# W506C.net
KiCad netlist of a schematic drawn in EAGLE
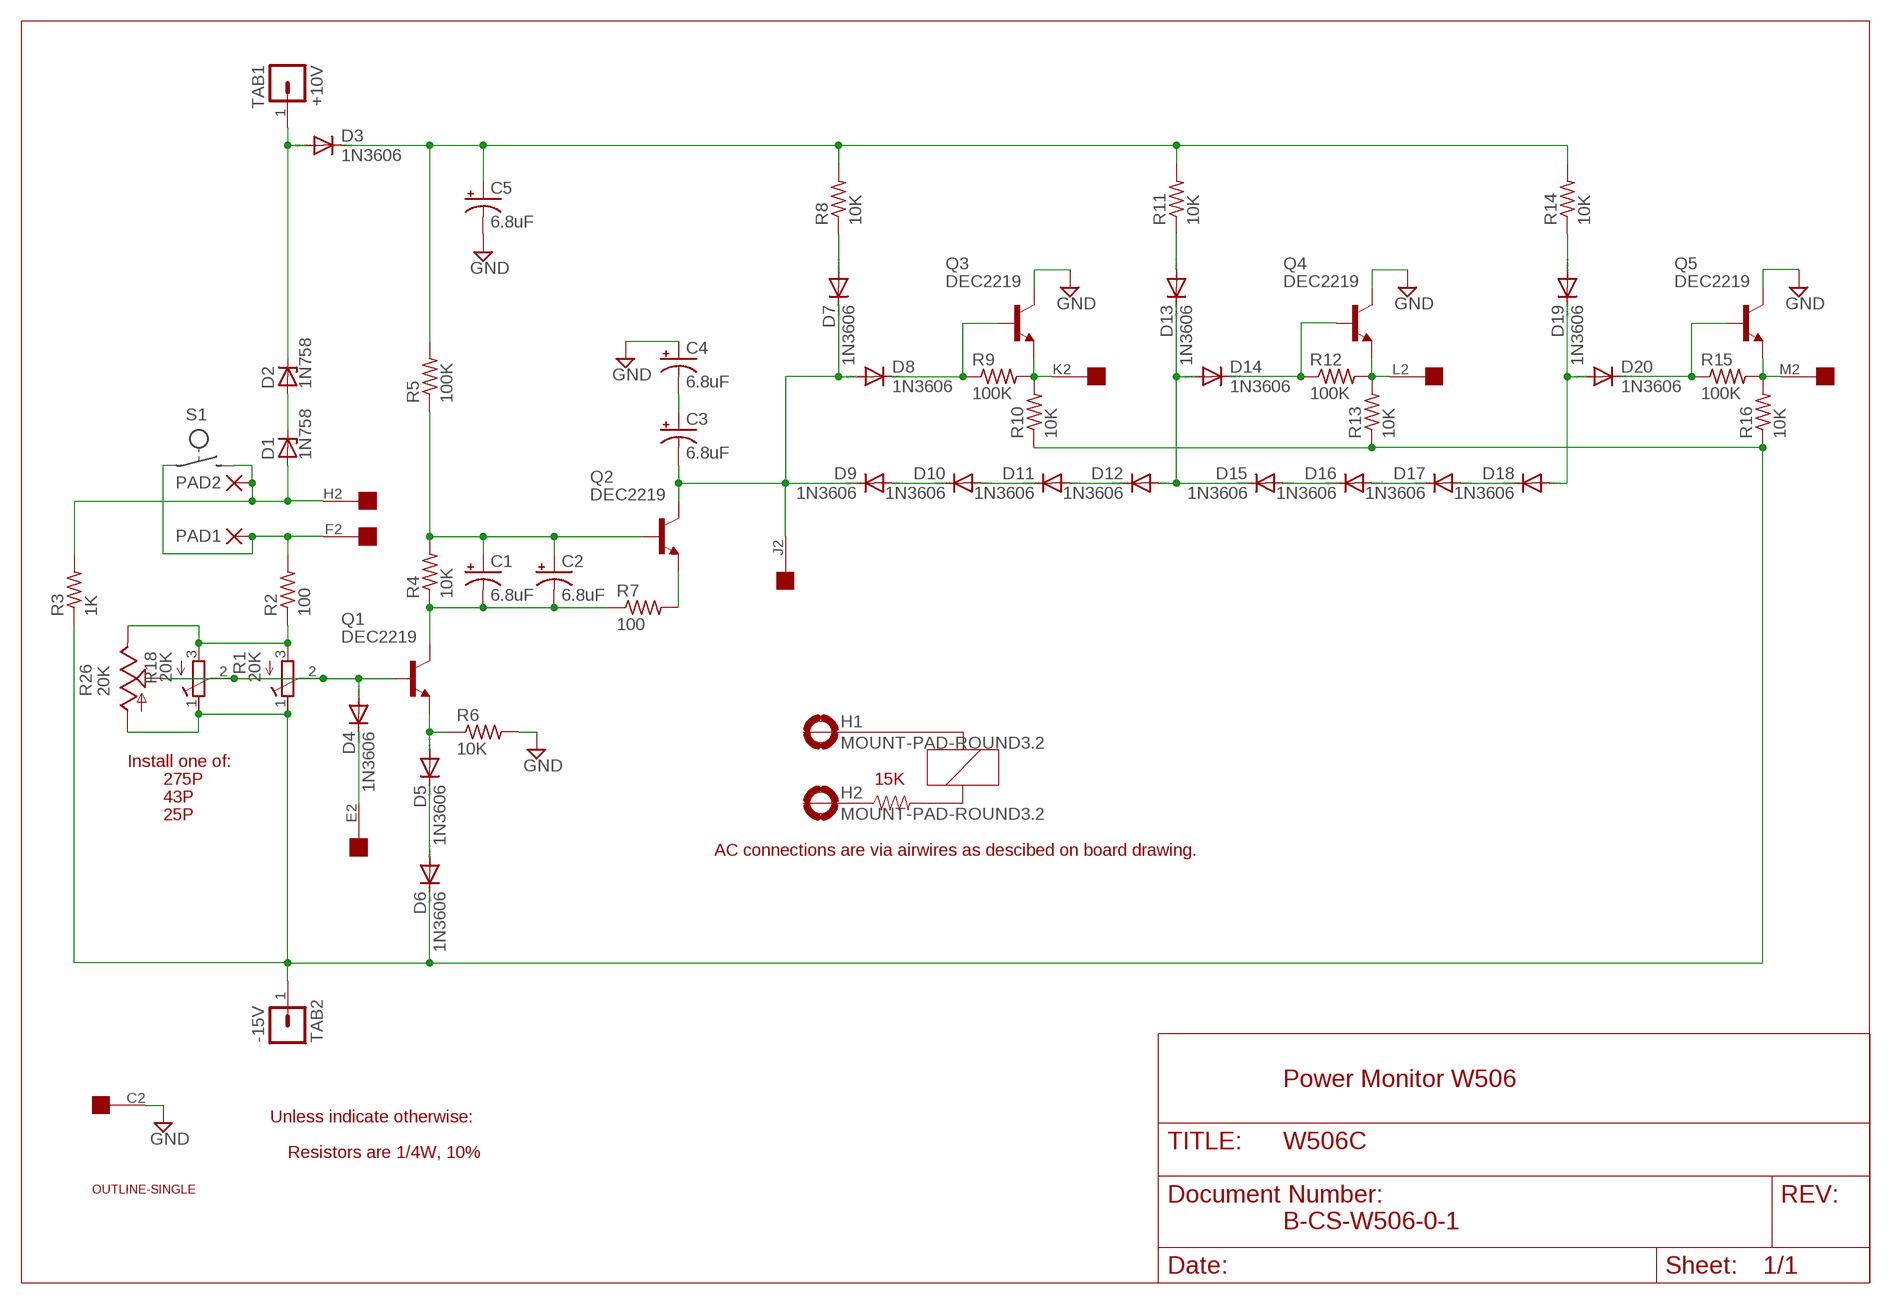
[diagram p0: schematic, sheet 1]

(export (version "E")
  (design (tool "Eeschema 10.0.6"))
  (components
    (comp (ref "C1")
      (value "6.8uF")
      (footprint "eagle-import:E15-5")
      (libsource (lib "eagle-import") (part "CPOL-USE15-5AXIAL"))
    )
    (comp (ref "C2")
      (value "6.8uF")
      (footprint "eagle-import:E15-5")
      (libsource (lib "eagle-import") (part "CPOL-USE15-5AXIAL"))
    )
    (comp (ref "C3")
      (value "6.8uF")
      (footprint "eagle-import:E15-5")
      (libsource (lib "eagle-import") (part "CPOL-USE15-5AXIAL"))
    )
    (comp (ref "C4")
      (value "6.8uF")
      (footprint "eagle-import:E15-5")
      (libsource (lib "eagle-import") (part "CPOL-USE15-5AXIAL"))
    )
    (comp (ref "C5")
      (value "6.8uF")
      (footprint "eagle-import:E15-5")
      (libsource (lib "eagle-import") (part "CPOL-USE15-5AXIAL"))
    )
    (comp (ref "D1")
      (value "1N758")
      (footprint "eagle-import:DO35Z10")
      (libsource (lib "eagle-import") (part "ZENER-DIODEDO35Z10"))
    )
    (comp (ref "D2")
      (value "1N758")
      (footprint "eagle-import:DO35Z10")
      (libsource (lib "eagle-import") (part "ZENER-DIODEDO35Z10"))
    )
    (comp (ref "D3")
      (value "1N3606")
      (footprint "eagle-import:DO35-10")
      (libsource (lib "eagle-import") (part "1N4148DO35-10"))
    )
    (comp (ref "D4")
      (value "1N3606")
      (footprint "eagle-import:DO35-10")
      (libsource (lib "eagle-import") (part "1N4148DO35-10"))
    )
    (comp (ref "D5")
      (value "1N3606")
      (footprint "eagle-import:DO35-10")
      (libsource (lib "eagle-import") (part "1N4148DO35-10"))
    )
    (comp (ref "D6")
      (value "1N3606")
      (footprint "eagle-import:DO35-10")
      (libsource (lib "eagle-import") (part "1N4148DO35-10"))
    )
    (comp (ref "D7")
      (value "1N3606")
      (footprint "eagle-import:DO35-10")
      (libsource (lib "eagle-import") (part "1N4148DO35-10"))
    )
    (comp (ref "D8")
      (value "1N3606")
      (footprint "eagle-import:DO35-10")
      (libsource (lib "eagle-import") (part "1N4148DO35-10"))
    )
    (comp (ref "D9")
      (value "1N3606")
      (footprint "eagle-import:DO35-10")
      (libsource (lib "eagle-import") (part "1N4148DO35-10"))
    )
    (comp (ref "D10")
      (value "1N3606")
      (footprint "eagle-import:DO35-10")
      (libsource (lib "eagle-import") (part "1N4148DO35-10"))
    )
    (comp (ref "D11")
      (value "1N3606")
      (footprint "eagle-import:DO35-10")
      (libsource (lib "eagle-import") (part "1N4148DO35-10"))
    )
    (comp (ref "D12")
      (value "1N3606")
      (footprint "eagle-import:DO35-10")
      (libsource (lib "eagle-import") (part "1N4148DO35-10"))
    )
    (comp (ref "D13")
      (value "1N3606")
      (footprint "eagle-import:DO35-10")
      (libsource (lib "eagle-import") (part "1N4148DO35-10"))
    )
    (comp (ref "D14")
      (value "1N3606")
      (footprint "eagle-import:DO35-10")
      (libsource (lib "eagle-import") (part "1N4148DO35-10"))
    )
    (comp (ref "D15")
      (value "1N3606")
      (footprint "eagle-import:DO35-10")
      (libsource (lib "eagle-import") (part "1N4148DO35-10"))
    )
    (comp (ref "D16")
      (value "1N3606")
      (footprint "eagle-import:DO35-10")
      (libsource (lib "eagle-import") (part "1N4148DO35-10"))
    )
    (comp (ref "D17")
      (value "1N3606")
      (footprint "eagle-import:DO35-10")
      (libsource (lib "eagle-import") (part "1N4148DO35-10"))
    )
    (comp (ref "D18")
      (value "1N3606")
      (footprint "eagle-import:DO35-10")
      (libsource (lib "eagle-import") (part "1N4148DO35-10"))
    )
    (comp (ref "D19")
      (value "1N3606")
      (footprint "eagle-import:DO35-10")
      (libsource (lib "eagle-import") (part "1N4148DO35-10"))
    )
    (comp (ref "D20")
      (value "1N3606")
      (footprint "eagle-import:DO35-10")
      (libsource (lib "eagle-import") (part "1N4148DO35-10"))
    )
    (comp (ref "EDGE")
      (value "EDGE-1")
      (footprint "eagle-import:EDGE-CON1")
      (libsource (lib "eagle-import") (part "EDGE-1"))
    )
    (comp (ref "H1")
      (value "MOUNT-PAD-ROUND3.2")
      (footprint "eagle-import:3,2-PAD")
      (libsource (lib "eagle-import") (part "MOUNT-PAD-ROUND3.2"))
    )
    (comp (ref "H2")
      (value "MOUNT-PAD-ROUND3.2")
      (footprint "eagle-import:3,2-PAD")
      (libsource (lib "eagle-import") (part "MOUNT-PAD-ROUND3.2"))
    )
    (comp (ref "PAD1")
      (value "PAD-0320")
      (footprint "eagle-import:0320")
      (libsource (lib "eagle-import") (part "PAD-0320"))
    )
    (comp (ref "PAD2")
      (value "PAD-0320")
      (footprint "eagle-import:0320")
      (libsource (lib "eagle-import") (part "PAD-0320"))
    )
    (comp (ref "Q1")
      (value "DEC2219")
      (footprint "eagle-import:TO5")
      (libsource (lib "eagle-import") (part "2N2102"))
    )
    (comp (ref "Q2")
      (value "DEC2219")
      (footprint "eagle-import:TO5")
      (libsource (lib "eagle-import") (part "2N2102"))
    )
    (comp (ref "Q3")
      (value "DEC2219")
      (footprint "eagle-import:TO5")
      (libsource (lib "eagle-import") (part "2N2102"))
    )
    (comp (ref "Q4")
      (value "DEC2219")
      (footprint "eagle-import:TO5")
      (libsource (lib "eagle-import") (part "2N2102"))
    )
    (comp (ref "Q5")
      (value "DEC2219")
      (footprint "eagle-import:TO5")
      (libsource (lib "eagle-import") (part "2N2102"))
    )
    (comp (ref "R1")
      (value "20K")
      (footprint "eagle-import:3006Y")
      (libsource (lib "eagle-import") (part "275P"))
    )
    (comp (ref "R2")
      (value "100")
      (footprint "eagle-import:0207_10")
      (libsource (lib "eagle-import") (part "R-US_0207/10"))
    )
    (comp (ref "R3")
      (value "1K")
      (footprint "eagle-import:0207_10")
      (libsource (lib "eagle-import") (part "R-US_0207/10"))
    )
    (comp (ref "R4")
      (value "10K")
      (footprint "eagle-import:0207_10")
      (libsource (lib "eagle-import") (part "R-US_0207/10"))
    )
    (comp (ref "R5")
      (value "100K")
      (footprint "eagle-import:0207_10")
      (libsource (lib "eagle-import") (part "R-US_0207/10"))
    )
    (comp (ref "R6")
      (value "10K")
      (footprint "eagle-import:0207_10")
      (libsource (lib "eagle-import") (part "R-US_0207/10"))
    )
    (comp (ref "R7")
      (value "100")
      (footprint "eagle-import:0207_10")
      (libsource (lib "eagle-import") (part "R-US_0207/10"))
    )
    (comp (ref "R8")
      (value "10K")
      (footprint "eagle-import:0207_10")
      (libsource (lib "eagle-import") (part "R-US_0207/10"))
    )
    (comp (ref "R9")
      (value "100K")
      (footprint "eagle-import:0207_10")
      (libsource (lib "eagle-import") (part "R-US_0207/10"))
    )
    (comp (ref "R10")
      (value "10K")
      (footprint "eagle-import:0207_10")
      (libsource (lib "eagle-import") (part "R-US_0207/10"))
    )
    (comp (ref "R11")
      (value "10K")
      (footprint "eagle-import:0207_10")
      (libsource (lib "eagle-import") (part "R-US_0207/10"))
    )
    (comp (ref "R12")
      (value "100K")
      (footprint "eagle-import:0207_10")
      (libsource (lib "eagle-import") (part "R-US_0207/10"))
    )
    (comp (ref "R13")
      (value "10K")
      (footprint "eagle-import:0207_10")
      (libsource (lib "eagle-import") (part "R-US_0207/10"))
    )
    (comp (ref "R14")
      (value "10K")
      (footprint "eagle-import:0207_10")
      (libsource (lib "eagle-import") (part "R-US_0207/10"))
    )
    (comp (ref "R15")
      (value "100K")
      (footprint "eagle-import:0207_10")
      (libsource (lib "eagle-import") (part "R-US_0207/10"))
    )
    (comp (ref "R16")
      (value "10K")
      (footprint "eagle-import:0207_10")
      (libsource (lib "eagle-import") (part "R-US_0207/10"))
    )
    (comp (ref "R18")
      (value "20K")
      (footprint "eagle-import:RTRIM43P")
      (libsource (lib "eagle-import") (part "R-TRIMM43P"))
    )
    (comp (ref "R26")
      (value "20K")
      (footprint "eagle-import:B25P")
      (libsource (lib "eagle-import") (part "TRIM_US-B25P"))
    )
    (comp (ref "TAB1")
      (value "+10V")
      (footprint "eagle-import:SPADELUG")
      (libsource (lib "eagle-import") (part "LUG"))
    )
    (comp (ref "TAB2")
      (value "-15V")
      (footprint "eagle-import:SPADELUG")
      (libsource (lib "eagle-import") (part "LUG"))
    )
    (comp (ref "U$1")
      (value "OUTLINE-SINGLE")
      (footprint "eagle-import:SINGLE")
      (libsource (lib "eagle-import") (part "OUTLINE-SINGLE"))
    )
  )
  (nets
    (net (code "1") (name "GND") (class "Default")
      (node (ref "C4") (pin "+") (pinfunction "+_+") (pintype "passive"))
      (node (ref "C5") (pin "-") (pinfunction "-_-") (pintype "passive"))
      (node (ref "EDGE") (pin "C2") (pinfunction "1_C2") (pintype "bidirectional"))
      (node (ref "Q3") (pin "3") (pinfunction "C_3") (pintype "passive"))
      (node (ref "Q4") (pin "3") (pinfunction "C_3") (pintype "passive"))
      (node (ref "Q5") (pin "3") (pinfunction "C_3") (pintype "passive"))
      (node (ref "R6") (pin "2") (pinfunction "2_2") (pintype "passive"))
    )
    (net (code "2") (name "Net-(C3-Pad+)") (class "Default")
      (node (ref "C3") (pin "+") (pinfunction "+_+") (pintype "passive"))
      (node (ref "C4") (pin "-") (pinfunction "-_-") (pintype "passive"))
    )
    (net (code "3") (name "Net-(C5-Pad+)") (class "Default")
      (node (ref "C5") (pin "+") (pinfunction "+_+") (pintype "passive"))
      (node (ref "D3") (pin "C") (pinfunction "C_C") (pintype "passive"))
      (node (ref "R11") (pin "2") (pinfunction "2_2") (pintype "passive"))
      (node (ref "R14") (pin "2") (pinfunction "2_2") (pintype "passive"))
      (node (ref "R5") (pin "2") (pinfunction "2_2") (pintype "passive"))
      (node (ref "R8") (pin "2") (pinfunction "2_2") (pintype "passive"))
    )
    (net (code "4") (name "Net-(D1-PadC)") (class "Default")
      (node (ref "D1") (pin "C") (pinfunction "C_C") (pintype "passive"))
      (node (ref "D2") (pin "A") (pinfunction "A_A") (pintype "passive"))
    )
    (net (code "5") (name "Net-(D2-PadC)") (class "Default")
      (node (ref "D2") (pin "C") (pinfunction "C_C") (pintype "passive"))
      (node (ref "D3") (pin "A") (pinfunction "A_A") (pintype "passive"))
      (node (ref "TAB1") (pin "1") (pinfunction "1_1") (pintype "passive"))
    )
    (net (code "6") (name "Net-(D5-PadC)") (class "Default")
      (node (ref "D5") (pin "C") (pinfunction "C_C") (pintype "passive"))
      (node (ref "D6") (pin "A") (pinfunction "A_A") (pintype "passive"))
    )
    (net (code "7") (name "Net-(D7-PadA)") (class "Default")
      (node (ref "D7") (pin "A") (pinfunction "A_A") (pintype "passive"))
      (node (ref "R8") (pin "1") (pinfunction "1_1") (pintype "passive"))
    )
    (net (code "8") (name "Net-(D10-PadA)") (class "Default")
      (node (ref "D10") (pin "A") (pinfunction "A_A") (pintype "passive"))
      (node (ref "D11") (pin "C") (pinfunction "C_C") (pintype "passive"))
    )
    (net (code "9") (name "Net-(D10-PadC)") (class "Default")
      (node (ref "D10") (pin "C") (pinfunction "C_C") (pintype "passive"))
      (node (ref "D9") (pin "A") (pinfunction "A_A") (pintype "passive"))
    )
    (net (code "10") (name "Net-(D11-PadA)") (class "Default")
      (node (ref "D11") (pin "A") (pinfunction "A_A") (pintype "passive"))
      (node (ref "D12") (pin "C") (pinfunction "C_C") (pintype "passive"))
    )
    (net (code "11") (name "Net-(D12-PadA)") (class "Default")
      (node (ref "D12") (pin "A") (pinfunction "A_A") (pintype "passive"))
      (node (ref "D13") (pin "C") (pinfunction "C_C") (pintype "passive"))
      (node (ref "D14") (pin "A") (pinfunction "A_A") (pintype "passive"))
      (node (ref "D15") (pin "C") (pinfunction "C_C") (pintype "passive"))
    )
    (net (code "12") (name "Net-(D13-PadA)") (class "Default")
      (node (ref "D13") (pin "A") (pinfunction "A_A") (pintype "passive"))
      (node (ref "R11") (pin "1") (pinfunction "1_1") (pintype "passive"))
    )
    (net (code "13") (name "Net-(D15-PadA)") (class "Default")
      (node (ref "D15") (pin "A") (pinfunction "A_A") (pintype "passive"))
      (node (ref "D16") (pin "C") (pinfunction "C_C") (pintype "passive"))
    )
    (net (code "14") (name "Net-(D16-PadA)") (class "Default")
      (node (ref "D16") (pin "A") (pinfunction "A_A") (pintype "passive"))
      (node (ref "D17") (pin "C") (pinfunction "C_C") (pintype "passive"))
    )
    (net (code "15") (name "Net-(D17-PadA)") (class "Default")
      (node (ref "D17") (pin "A") (pinfunction "A_A") (pintype "passive"))
      (node (ref "D18") (pin "C") (pinfunction "C_C") (pintype "passive"))
    )
    (net (code "16") (name "Net-(D18-PadA)") (class "Default")
      (node (ref "D18") (pin "A") (pinfunction "A_A") (pintype "passive"))
      (node (ref "D19") (pin "C") (pinfunction "C_C") (pintype "passive"))
      (node (ref "D20") (pin "A") (pinfunction "A_A") (pintype "passive"))
    )
    (net (code "17") (name "Net-(D19-PadA)") (class "Default")
      (node (ref "D19") (pin "A") (pinfunction "A_A") (pintype "passive"))
      (node (ref "R14") (pin "1") (pinfunction "1_1") (pintype "passive"))
    )
    (net (code "18") (name "Net-(EDGEE-1)") (class "Default")
      (node (ref "D4") (pin "C") (pinfunction "C_C") (pintype "passive"))
      (node (ref "EDGE") (pin "E2") (pinfunction "1_E2") (pintype "bidirectional"))
    )
    (net (code "19") (name "Net-(EDGEF-1)") (class "Default")
      (node (ref "EDGE") (pin "F2") (pinfunction "1_F2") (pintype "bidirectional"))
      (node (ref "PAD1") (pin "P$1") (pinfunction "P_P$1") (pintype "passive"))
      (node (ref "R2") (pin "2") (pinfunction "2_2") (pintype "passive"))
    )
    (net (code "20") (name "Net-(EDGEG-1)") (class "Default")
      (node (ref "D1") (pin "A") (pinfunction "A_A") (pintype "passive"))
      (node (ref "EDGE") (pin "H2") (pinfunction "1_H2") (pintype "bidirectional"))
      (node (ref "PAD2") (pin "P$1") (pinfunction "P_P$1") (pintype "passive"))
      (node (ref "R3") (pin "2") (pinfunction "2_2") (pintype "passive"))
    )
    (net (code "21") (name "Net-(EDGEH-1)") (class "Default")
      (node (ref "C3") (pin "-") (pinfunction "-_-") (pintype "passive"))
      (node (ref "D7") (pin "C") (pinfunction "C_C") (pintype "passive"))
      (node (ref "D8") (pin "A") (pinfunction "A_A") (pintype "passive"))
      (node (ref "D9") (pin "C") (pinfunction "C_C") (pintype "passive"))
      (node (ref "EDGE") (pin "J2") (pinfunction "1_J2") (pintype "bidirectional"))
      (node (ref "Q2") (pin "3") (pinfunction "C_3") (pintype "passive"))
    )
    (net (code "22") (name "Net-(EDGEI-1)") (class "Default")
      (node (ref "EDGE") (pin "K2") (pinfunction "1_K2") (pintype "bidirectional"))
      (node (ref "Q3") (pin "1") (pinfunction "E_1") (pintype "passive"))
      (node (ref "R10") (pin "2") (pinfunction "2_2") (pintype "passive"))
      (node (ref "R9") (pin "2") (pinfunction "2_2") (pintype "passive"))
    )
    (net (code "23") (name "Net-(EDGEJ-1)") (class "Default")
      (node (ref "EDGE") (pin "L2") (pinfunction "1_L2") (pintype "bidirectional"))
      (node (ref "Q4") (pin "1") (pinfunction "E_1") (pintype "passive"))
      (node (ref "R12") (pin "2") (pinfunction "2_2") (pintype "passive"))
      (node (ref "R13") (pin "2") (pinfunction "2_2") (pintype "passive"))
    )
    (net (code "24") (name "Net-(EDGEK-1)") (class "Default")
      (node (ref "EDGE") (pin "M2") (pinfunction "1_M2") (pintype "bidirectional"))
      (node (ref "Q5") (pin "1") (pinfunction "E_1") (pintype "passive"))
      (node (ref "R15") (pin "2") (pinfunction "2_2") (pintype "passive"))
      (node (ref "R16") (pin "2") (pinfunction "2_2") (pintype "passive"))
    )
    (net (code "25") (name "Net-(Q1-B)") (class "Default")
      (node (ref "D4") (pin "A") (pinfunction "A_A") (pintype "passive"))
      (node (ref "Q1") (pin "2") (pinfunction "B_2") (pintype "passive"))
      (node (ref "R1") (pin "2") (pinfunction "S_2") (pintype "passive"))
      (node (ref "R18") (pin "2") (pinfunction "S_2") (pintype "passive"))
      (node (ref "R26") (pin "S") (pinfunction "S_S") (pintype "passive"))
    )
    (net (code "26") (name "Net-(Q1-C)") (class "Default")
      (node (ref "C1") (pin "-") (pinfunction "-_-") (pintype "passive"))
      (node (ref "C2") (pin "-") (pinfunction "-_-") (pintype "passive"))
      (node (ref "Q1") (pin "3") (pinfunction "C_3") (pintype "passive"))
      (node (ref "R4") (pin "1") (pinfunction "1_1") (pintype "passive"))
      (node (ref "R7") (pin "1") (pinfunction "1_1") (pintype "passive"))
    )
    (net (code "27") (name "Net-(Q1-E)") (class "Default")
      (node (ref "D5") (pin "A") (pinfunction "A_A") (pintype "passive"))
      (node (ref "Q1") (pin "1") (pinfunction "E_1") (pintype "passive"))
      (node (ref "R6") (pin "1") (pinfunction "1_1") (pintype "passive"))
    )
    (net (code "28") (name "Net-(Q2-B)") (class "Default")
      (node (ref "C1") (pin "+") (pinfunction "+_+") (pintype "passive"))
      (node (ref "C2") (pin "+") (pinfunction "+_+") (pintype "passive"))
      (node (ref "Q2") (pin "2") (pinfunction "B_2") (pintype "passive"))
      (node (ref "R4") (pin "2") (pinfunction "2_2") (pintype "passive"))
      (node (ref "R5") (pin "1") (pinfunction "1_1") (pintype "passive"))
    )
    (net (code "29") (name "Net-(Q2-E)") (class "Default")
      (node (ref "Q2") (pin "1") (pinfunction "E_1") (pintype "passive"))
      (node (ref "R7") (pin "2") (pinfunction "2_2") (pintype "passive"))
    )
    (net (code "30") (name "Net-(Q3-B)") (class "Default")
      (node (ref "D8") (pin "C") (pinfunction "C_C") (pintype "passive"))
      (node (ref "Q3") (pin "2") (pinfunction "B_2") (pintype "passive"))
      (node (ref "R9") (pin "1") (pinfunction "1_1") (pintype "passive"))
    )
    (net (code "31") (name "Net-(Q4-B)") (class "Default")
      (node (ref "D14") (pin "C") (pinfunction "C_C") (pintype "passive"))
      (node (ref "Q4") (pin "2") (pinfunction "B_2") (pintype "passive"))
      (node (ref "R12") (pin "1") (pinfunction "1_1") (pintype "passive"))
    )
    (net (code "32") (name "Net-(Q5-B)") (class "Default")
      (node (ref "D20") (pin "C") (pinfunction "C_C") (pintype "passive"))
      (node (ref "Q5") (pin "2") (pinfunction "B_2") (pintype "passive"))
      (node (ref "R15") (pin "1") (pinfunction "1_1") (pintype "passive"))
    )
    (net (code "33") (name "Net-(R1-A)") (class "Default")
      (node (ref "D6") (pin "C") (pinfunction "C_C") (pintype "passive"))
      (node (ref "R1") (pin "1") (pinfunction "A_1") (pintype "passive"))
      (node (ref "R10") (pin "1") (pinfunction "1_1") (pintype "passive"))
      (node (ref "R13") (pin "1") (pinfunction "1_1") (pintype "passive"))
      (node (ref "R16") (pin "1") (pinfunction "1_1") (pintype "passive"))
      (node (ref "R18") (pin "1") (pinfunction "E_1") (pintype "passive"))
      (node (ref "R26") (pin "A") (pinfunction "A_A") (pintype "passive"))
      (node (ref "R3") (pin "1") (pinfunction "1_1") (pintype "passive"))
      (node (ref "TAB2") (pin "1") (pinfunction "1_1") (pintype "passive"))
    )
    (net (code "34") (name "Net-(R1-E)") (class "Default")
      (node (ref "R1") (pin "3") (pinfunction "E_3") (pintype "passive"))
      (node (ref "R18") (pin "3") (pinfunction "A_3") (pintype "passive"))
      (node (ref "R2") (pin "1") (pinfunction "1_1") (pintype "passive"))
      (node (ref "R26") (pin "E") (pinfunction "E_E") (pintype "passive"))
    )
    (net (code "35") (name "unconnected-(H1-MOUNT-PadB3,2)") (class "Default")
      (node (ref "H1") (pin "B3,2") (pinfunction "MOUNT_B3,2") (pintype "passive"))
    )
    (net (code "36") (name "unconnected-(H2-MOUNT-PadB3,2)") (class "Default")
      (node (ref "H2") (pin "B3,2") (pinfunction "MOUNT_B3,2") (pintype "passive"))
    )
  )
)
